# Sheet1.net
KiCad netlist of a schematic drawn in Altium Designer
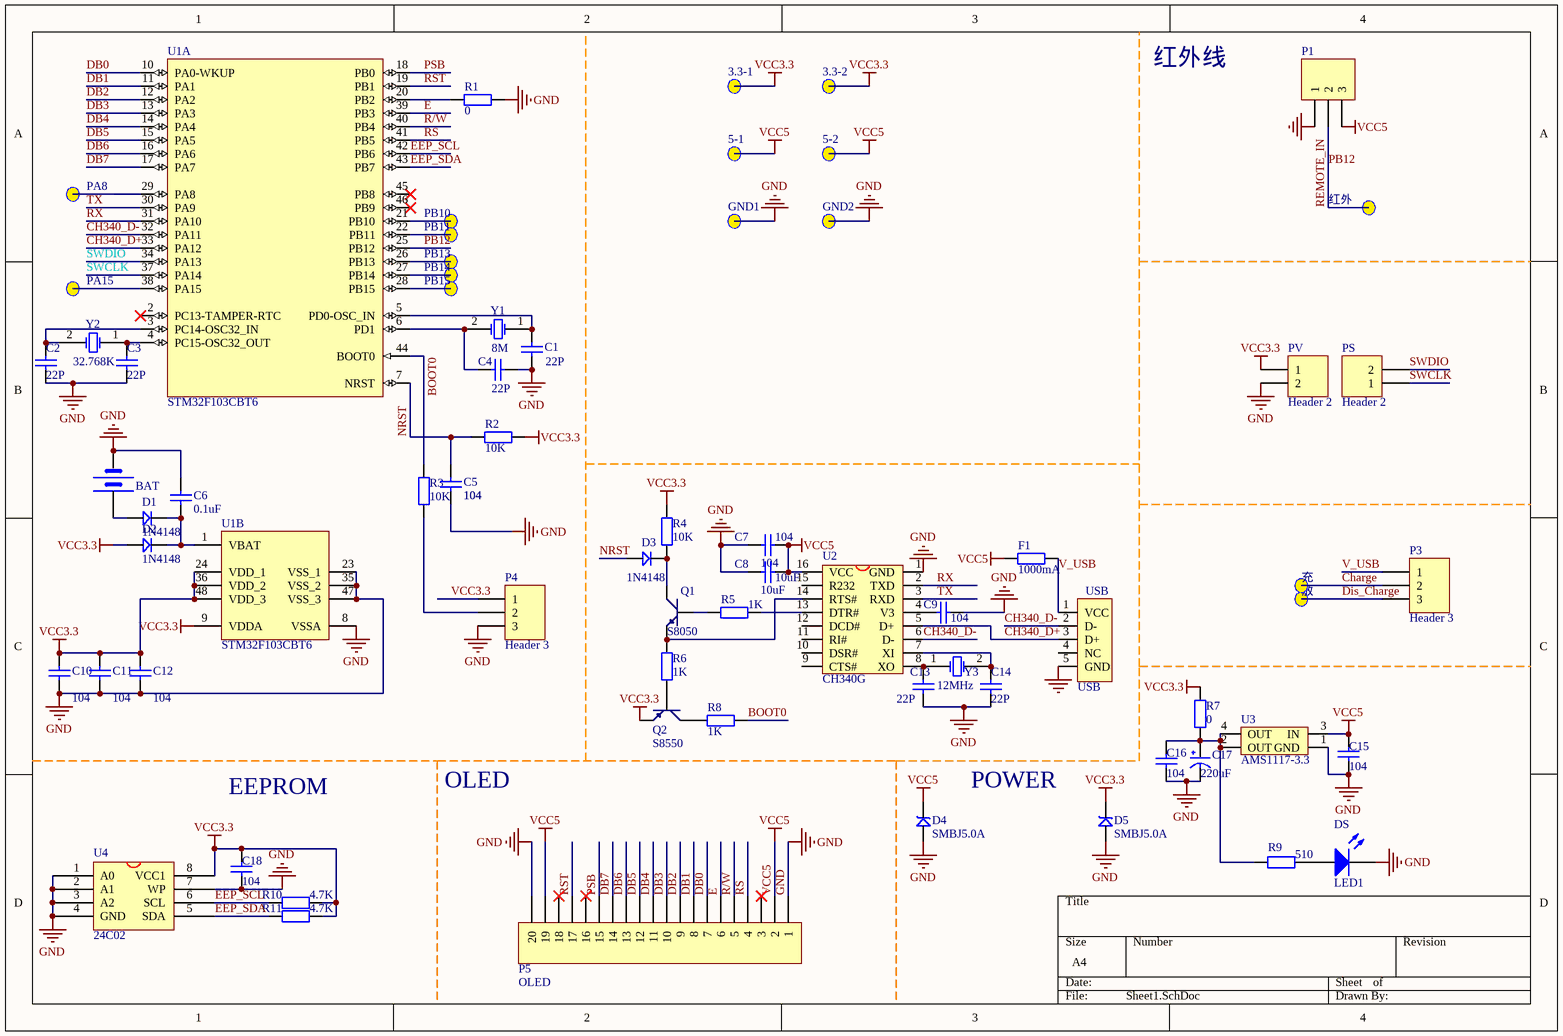
[diagram p0: Sheet1.SchDoc]

(export (version "E")
  (design (tool "Eeschema 10.0.6"))
  (components
    (comp (ref "3.3-1")
      (value "TEST_PAD")
      (footprint "pin1")
      (libsource (lib "EliteSTM32") (part "TEST_PAD"))
    )
    (comp (ref "3.3-2")
      (value "TEST_PAD")
      (footprint "pin1")
      (libsource (lib "EliteSTM32") (part "TEST_PAD"))
    )
    (comp (ref "5-1") (value "TEST_PAD") (footprint "pin1") (libsource (lib "EliteSTM32") (part "TEST_PAD")))
    (comp (ref "5-2") (value "TEST_PAD") (footprint "pin1") (libsource (lib "EliteSTM32") (part "TEST_PAD")))
    (comp (ref "BAT") (value "BATT") (footprint "BATM") (libsource (lib "EliteSTM32封装库") (part "BAT")))
    (comp (ref "C1")
      (value "22P")
      (footprint "0603p")
      (description "Capacitor")
      (fields (field (name "PUBLISHER") "Altium Limited"))
      (libsource (lib "Miscellaneous Devices") (part "Cap"))
    )
    (comp (ref "C2")
      (value "22P")
      (footprint "0603P")
      (description "Capacitor")
      (fields (field (name "PUBLISHER") "Altium Limited"))
      (libsource (lib "Miscellaneous Devices") (part "Cap"))
    )
    (comp (ref "C3")
      (value "22P")
      (footprint "0603P")
      (description "Capacitor")
      (fields (field (name "PUBLISHER") "Altium Limited"))
      (libsource (lib "Miscellaneous Devices") (part "Cap"))
    )
    (comp (ref "C4")
      (value "22P")
      (footprint "0603p")
      (description "Capacitor")
      (fields (field (name "PUBLISHER") "Altium Limited"))
      (libsource (lib "Miscellaneous Devices") (part "Cap"))
    )
    (comp (ref "C5")
      (value "104")
      (footprint "0603p")
      (description "Capacitor")
      (fields (field (name "ALTIUM_VALUE") "104") (field (name "PUBLISHER") "Altium Limited"))
      (libsource (lib "Miscellaneous Devices") (part "Cap"))
    )
    (comp (ref "C6")
      (value "0.1uF")
      (footprint "0603P")
      (description "Capacitor")
      (fields (field (name "PUBLISHER") "Altium Limited"))
      (libsource (lib "Miscellaneous Devices") (part "Cap"))
    )
    (comp (ref "C7")
      (value "104")
      (footprint "0603p")
      (description "Capacitor")
      (fields (field (name "ALTIUM_VALUE") "104") (field (name "PUBLISHER") "Altium Limited"))
      (libsource (lib "Miscellaneous Devices") (part "Cap"))
    )
    (comp (ref "C8")
      (value "10uF")
      (footprint "0603p")
      (description "Capacitor")
      (fields (field (name "ALTIUM_VALUE") "10uF") (field (name "PUBLISHER") "Altium Limited"))
      (libsource (lib "Miscellaneous Devices") (part "Cap"))
    )
    (comp (ref "C9")
      (value "104")
      (footprint "0603P")
      (description "Capacitor")
      (fields (field (name "PUBLISHER") "Altium Limited"))
      (libsource (lib "Miscellaneous Devices") (part "Cap"))
    )
    (comp (ref "C10")
      (value "104")
      (footprint "0603p")
      (description "Capacitor")
      (fields (field (name "PUBLISHER") "Altium Limited"))
      (libsource (lib "Miscellaneous Devices") (part "Cap"))
    )
    (comp (ref "C11")
      (value "104")
      (footprint "0603p")
      (description "Capacitor")
      (fields (field (name "PUBLISHER") "Altium Limited"))
      (libsource (lib "Miscellaneous Devices") (part "Cap"))
    )
    (comp (ref "C12")
      (value "104")
      (footprint "0603p")
      (description "Capacitor")
      (fields (field (name "PUBLISHER") "Altium Limited"))
      (libsource (lib "Miscellaneous Devices") (part "Cap"))
    )
    (comp (ref "C13")
      (value "22P")
      (footprint "0603P")
      (description "Capacitor")
      (fields (field (name "PUBLISHER") "Altium Limited"))
      (libsource (lib "Miscellaneous Devices") (part "Cap"))
    )
    (comp (ref "C14")
      (value "22P")
      (footprint "0603P")
      (description "Capacitor")
      (fields (field (name "PUBLISHER") "Altium Limited"))
      (libsource (lib "Miscellaneous Devices") (part "Cap"))
    )
    (comp (ref "C15")
      (value "104")
      (footprint "0603P")
      (description "Capacitor")
      (fields (field (name "PUBLISHER") "Altium Limited"))
      (libsource (lib "Miscellaneous Devices") (part "Cap"))
    )
    (comp (ref "C16")
      (value "104")
      (footprint "0603P")
      (description "Capacitor")
      (fields (field (name "PUBLISHER") "Altium Limited"))
      (libsource (lib "Miscellaneous Devices") (part "Cap"))
    )
    (comp (ref "C17") (value "220uF") (footprint "CC6.56.5") (libsource (lib "EliteSTM32封装库") (part "CAP")))
    (comp (ref "C18")
      (value "104")
      (footprint "0603P")
      (description "Capacitor")
      (fields (field (name "PUBLISHER") "Altium Limited"))
      (libsource (lib "Miscellaneous Devices") (part "Cap"))
    )
    (comp (ref "D1") (value "1N4148") (footprint "DIODE_SOP") (libsource (lib "EliteSTM32封装库") (part "D")))
    (comp (ref "D2") (value "1N4148") (footprint "DIODE_SOP") (libsource (lib "EliteSTM32封装库") (part "D")))
    (comp (ref "D3") (value "1N4148") (footprint "DIODE_SOP") (libsource (lib "EliteSTM32封装库") (part "D")))
    (comp (ref "D4")
      (value "SMBJ5.0A")
      (footprint "SMBJ")
      (description "TVS")
      (libsource (lib "EliteSTM32封装库") (part "SMBJ"))
    )
    (comp (ref "D5")
      (value "SMBJ5.0A")
      (footprint "SMBJ")
      (description "TVS")
      (libsource (lib "EliteSTM32封装库") (part "SMBJ"))
    )
    (comp (ref "DS")
      (value "LED1")
      (footprint "SMDLED")
      (description "Typical RED, GREEN, YELLOW, AMBER GaAs LED")
      (fields (field (name "PUBLISHER") "Altium Limited"))
      (libsource (lib "EliteSTM32封装库") (part "LED2"))
    )
    (comp (ref "F1")
      (value "1000mA")
      (footprint "1206")
      (description "Resistor")
      (fields (field (name "PUBLISHER") "Altium Limited"))
      (libsource (lib "") (part "Res2_1"))
    )
    (comp (ref "GND1") (value "TEST_PAD") (footprint "pin1") (libsource (lib "EliteSTM32") (part "TEST_PAD")))
    (comp (ref "GND2") (value "TEST_PAD") (footprint "pin1") (libsource (lib "EliteSTM32") (part "TEST_PAD")))
    (comp (ref "P1")
      (value "Header 3")
      (footprint "HDR1X3")
      (description "Header, 3-Pin")
      (fields (field (name "PUBLISHER") "Altium Limited"))
      (libsource (lib "") (part "Header 3_1"))
    )
    (comp (ref "P3")
      (value "Header 3")
      (footprint "HDR1X3")
      (description "Header, 3-Pin")
      (fields (field (name "PUBLISHER") "Altium Limited"))
      (libsource (lib "Miscellaneous Connectors") (part "Header 3"))
    )
    (comp (ref "P4")
      (value "Header 3")
      (footprint "2-1")
      (description "Header, 3-Pin")
      (fields (field (name "PUBLISHER") "Altium Limited"))
      (libsource (lib "Miscellaneous Connectors") (part "Header 3"))
    )
    (comp (ref "P5")
      (value "OLED")
      (footprint "HDR1X20")
      (description "Header, 20-Pin")
      (fields (field (name "PUBLISHER") "Altium Limited"))
      (libsource (lib "Miscellaneous Connectors") (part "Header 20"))
    )
    (comp (ref "PA8") (value "TEST_PAD") (footprint "pin1") (libsource (lib "EliteSTM32") (part "TEST_PAD")))
    (comp (ref "PA15") (value "TEST_PAD") (footprint "pin1") (libsource (lib "EliteSTM32") (part "TEST_PAD")))
    (comp (ref "PB10") (value "TEST_PAD") (footprint "pin1") (libsource (lib "EliteSTM32") (part "TEST_PAD")))
    (comp (ref "PB11") (value "TEST_PAD") (footprint "pin1") (libsource (lib "EliteSTM32") (part "TEST_PAD")))
    (comp (ref "PB13") (value "TEST_PAD") (footprint "pin1") (libsource (lib "EliteSTM32") (part "TEST_PAD")))
    (comp (ref "PB14") (value "TEST_PAD") (footprint "pin1") (libsource (lib "EliteSTM32") (part "TEST_PAD")))
    (comp (ref "PB15") (value "TEST_PAD") (footprint "pin1") (libsource (lib "EliteSTM32") (part "TEST_PAD")))
    (comp (ref "PS")
      (value "Header 2")
      (footprint "HDR1X2")
      (description "Header, 2-Pin")
      (fields (field (name "PUBLISHER") "Altium Limited"))
      (libsource (lib "Miscellaneous Connectors") (part "Header 2"))
    )
    (comp (ref "PV")
      (value "Header 2")
      (footprint "HDR1X2")
      (description "Header, 2-Pin")
      (fields (field (name "PUBLISHER") "Altium Limited"))
      (libsource (lib "") (part "Header 2_1"))
    )
    (comp (ref "Q1")
      (value "S8050")
      (footprint "SOT-23R")
      (description "8050/BCW846/BCW847")
      (libsource (lib "EliteSTM32") (part "NPN"))
    )
    (comp (ref "Q2")
      (value "S8550")
      (footprint "SOT-23R")
      (description "8550/BCW68")
      (libsource (lib "EliteSTM32") (part "PNP"))
    )
    (comp (ref "R1")
      (value "0")
      (footprint "0603p")
      (description "Resistor")
      (fields (field (name "PUBLISHER") "Altium Limited"))
      (libsource (lib "Miscellaneous Devices") (part "Res2"))
    )
    (comp (ref "R2")
      (value "10K")
      (footprint "0603p")
      (description "Resistor")
      (fields (field (name "PUBLISHER") "Altium Limited"))
      (libsource (lib "Miscellaneous Devices") (part "Res2"))
    )
    (comp (ref "R3")
      (value "10K")
      (footprint "0603p")
      (description "Resistor")
      (fields (field (name "PUBLISHER") "Altium Limited"))
      (libsource (lib "") (part "Res2_2"))
    )
    (comp (ref "R4")
      (value "10K")
      (footprint "0603p")
      (description "Resistor")
      (fields (field (name "PUBLISHER") "Altium Limited"))
      (libsource (lib "") (part "Res2_2"))
    )
    (comp (ref "R5")
      (value "1K")
      (footprint "0603p")
      (description "Resistor")
      (fields (field (name "PUBLISHER") "Altium Limited"))
      (libsource (lib "Miscellaneous Devices") (part "Res2"))
    )
    (comp (ref "R6")
      (value "1K")
      (footprint "0603p")
      (description "Resistor")
      (fields (field (name "PUBLISHER") "Altium Limited"))
      (libsource (lib "") (part "Res2_2"))
    )
    (comp (ref "R7")
      (value "0")
      (footprint "0603P")
      (description "Resistor")
      (fields (field (name "PUBLISHER") "Altium Limited"))
      (libsource (lib "") (part "Res2_2"))
    )
    (comp (ref "R8")
      (value "1K")
      (footprint "0603p")
      (description "Resistor")
      (fields (field (name "PUBLISHER") "Altium Limited"))
      (libsource (lib "") (part "Res2_1"))
    )
    (comp (ref "R9")
      (value "510")
      (footprint "0603p")
      (description "Resistor")
      (fields (field (name "PUBLISHER") "Altium Limited"))
      (libsource (lib "Miscellaneous Devices") (part "Res2"))
    )
    (comp (ref "R10")
      (value "4.7K")
      (footprint "0603P")
      (description "Resistor")
      (fields (field (name "PUBLISHER") "Altium Limited"))
      (libsource (lib "Miscellaneous Devices") (part "Res2"))
    )
    (comp (ref "R11")
      (value "4.7K")
      (footprint "0603P")
      (description "Resistor")
      (fields (field (name "PUBLISHER") "Altium Limited"))
      (libsource (lib "Miscellaneous Devices") (part "Res2"))
    )
    (comp (ref "U1")
      (value "STM32F103CBT6")
      (footprint "LQFP48_M")
      (libsource (lib "STMicroelectronics STM32 F1") (part "STM32F103CBT6"))
    )
    (comp (ref "U2")
      (value "CH340G")
      (footprint "SOP16M")
      (description "USB2UART")
      (libsource (lib "EliteSTM32") (part "CH340G"))
    )
    (comp (ref "U3")
      (value "AMS1117-3.3")
      (footprint "AMS1117")
      (libsource (lib "EliteSTM32封装库") (part "AMS1117"))
    )
    (comp (ref "U4") (value "24C02") (footprint "SOP-8") (libsource (lib "cabinet") (part "24C256")))
    (comp (ref "USB")
      (value "USB")
      (footprint "USB/SM0.8-6H5")
      (libsource (lib "EliteSTM32封装库") (part "USB5"))
    )
    (comp (ref "Y1")
      (value "8M")
      (footprint "XTAL_US")
      (description "Crystal Oscillator")
      (fields (field (name "PUBLISHER") "Altium Limited"))
      (libsource (lib "Miscellaneous Devices") (part "XTAL"))
    )
    (comp (ref "Y2")
      (value "32.768K")
      (footprint "XTAL32")
      (description "Crystal Oscillator")
      (fields (field (name "PUBLISHER") "Altium Limited"))
      (libsource (lib "Miscellaneous Devices") (part "XTAL"))
    )
    (comp (ref "Y3")
      (value "12MHz")
      (footprint "XTAL_US")
      (description "Crystal Oscillator")
      (fields (field (name "PUBLISHER") "Altium Limited"))
      (libsource (lib "EliteSTM32") (part "XTAL"))
    )
    (comp (ref "充") (value "TEST_PAD") (footprint "pin1") (libsource (lib "EliteSTM32") (part "TEST_PAD")))
    (comp (ref "放") (value "TEST_PAD") (footprint "pin1") (libsource (lib "EliteSTM32") (part "TEST_PAD")))
    (comp (ref "红外") (value "TEST_PAD") (footprint "pin1") (libsource (lib "EliteSTM32") (part "TEST_PAD")))
  )
  (nets
    (net (code "1") (name "/BOOT0") (class "Default")
      (node (ref "R3") (pin "2") (pinfunction "2_2") (pintype "passive"))
      (node (ref "R8") (pin "1") (pinfunction "1_1") (pintype "passive"))
      (node (ref "U1") (pin "44") (pinfunction "BOOT0_44") (pintype "input"))
    )
    (net (code "2") (name "/CH340_D+") (class "Default")
      (node (ref "U1") (pin "33") (pinfunction "PA12_33") (pintype "bidirectional"))
      (node (ref "U2") (pin "5") (pinfunction "D+_5") (pintype "passive"))
      (node (ref "USB") (pin "3") (pinfunction "D+_3") (pintype "passive"))
    )
    (net (code "3") (name "/CH340_D-") (class "Default")
      (node (ref "U1") (pin "32") (pinfunction "PA11_32") (pintype "bidirectional"))
      (node (ref "U2") (pin "6") (pinfunction "D-_6") (pintype "passive"))
      (node (ref "USB") (pin "2") (pinfunction "D-_2") (pintype "passive"))
    )
    (net (code "4") (name "/Charge") (class "Default")
      (node (ref "P3") (pin "2") (pinfunction "2_2") (pintype "passive"))
      (node (ref "充") (pin "1") (pinfunction "1_1") (pintype "passive"))
    )
    (net (code "5") (name "/DB0") (class "Default")
      (node (ref "P5") (pin "7") (pinfunction "7_7") (pintype "passive"))
      (node (ref "U1") (pin "10") (pinfunction "PA0-WKUP_10") (pintype "bidirectional"))
    )
    (net (code "6") (name "/DB1") (class "Default")
      (node (ref "P5") (pin "8") (pinfunction "8_8") (pintype "passive"))
      (node (ref "U1") (pin "11") (pinfunction "PA1_11") (pintype "bidirectional"))
    )
    (net (code "7") (name "/DB2") (class "Default")
      (node (ref "P5") (pin "9") (pinfunction "9_9") (pintype "passive"))
      (node (ref "U1") (pin "12") (pinfunction "PA2_12") (pintype "bidirectional"))
    )
    (net (code "8") (name "/DB3") (class "Default")
      (node (ref "P5") (pin "10") (pinfunction "10_10") (pintype "passive"))
      (node (ref "U1") (pin "13") (pinfunction "PA3_13") (pintype "bidirectional"))
    )
    (net (code "9") (name "/DB4") (class "Default")
      (node (ref "P5") (pin "11") (pinfunction "11_11") (pintype "passive"))
      (node (ref "U1") (pin "14") (pinfunction "PA4_14") (pintype "bidirectional"))
    )
    (net (code "10") (name "/DB5") (class "Default")
      (node (ref "P5") (pin "12") (pinfunction "12_12") (pintype "passive"))
      (node (ref "U1") (pin "15") (pinfunction "PA5_15") (pintype "bidirectional"))
    )
    (net (code "11") (name "/DB6") (class "Default")
      (node (ref "P5") (pin "13") (pinfunction "13_13") (pintype "passive"))
      (node (ref "U1") (pin "16") (pinfunction "PA6_16") (pintype "bidirectional"))
    )
    (net (code "12") (name "/DB7") (class "Default")
      (node (ref "P5") (pin "14") (pinfunction "14_14") (pintype "passive"))
      (node (ref "U1") (pin "17") (pinfunction "PA7_17") (pintype "bidirectional"))
    )
    (net (code "13") (name "/Dis_Charge") (class "Default")
      (node (ref "P3") (pin "3") (pinfunction "3_3") (pintype "passive"))
      (node (ref "放") (pin "1") (pinfunction "1_1") (pintype "passive"))
    )
    (net (code "14") (name "/E") (class "Default")
      (node (ref "P5") (pin "6") (pinfunction "6_6") (pintype "passive"))
      (node (ref "U1") (pin "39") (pinfunction "PB3_39") (pintype "bidirectional"))
    )
    (net (code "15") (name "/EEP_SCL") (class "Default")
      (node (ref "R10") (pin "1") (pinfunction "1_1") (pintype "passive"))
      (node (ref "U1") (pin "42") (pinfunction "PB6_42") (pintype "bidirectional"))
      (node (ref "U4") (pin "6") (pinfunction "SCL_6") (pintype "passive"))
    )
    (net (code "16") (name "/EEP_SDA") (class "Default")
      (node (ref "R11") (pin "1") (pinfunction "1_1") (pintype "passive"))
      (node (ref "U1") (pin "43") (pinfunction "PB7_43") (pintype "bidirectional"))
      (node (ref "U4") (pin "5") (pinfunction "SDA_5") (pintype "passive"))
    )
    (net (code "17") (name "/NRST") (class "Default")
      (node (ref "C5") (pin "2") (pinfunction "2_2") (pintype "passive"))
      (node (ref "D3") (pin "1") (pintype "passive"))
      (node (ref "R2") (pin "1") (pinfunction "1_1") (pintype "passive"))
      (node (ref "U1") (pin "7") (pinfunction "NRST_7") (pintype "bidirectional"))
    )
    (net (code "18") (name "/PB12") (class "Default")
      (node (ref "P1") (pin "2") (pinfunction "2_2") (pintype "passive"))
      (node (ref "U1") (pin "25") (pinfunction "PB12_25") (pintype "bidirectional"))
      (node (ref "红外") (pin "1") (pinfunction "1_1") (pintype "passive"))
    )
    (net (code "19") (name "/PSB") (class "Default")
      (node (ref "P5") (pin "15") (pinfunction "15_15") (pintype "passive"))
      (node (ref "U1") (pin "18") (pinfunction "PB0_18") (pintype "bidirectional"))
    )
    (net (code "20") (name "/RS") (class "Default")
      (node (ref "P5") (pin "4") (pinfunction "4_4") (pintype "passive"))
      (node (ref "U1") (pin "41") (pinfunction "PB5_41") (pintype "bidirectional"))
    )
    (net (code "21") (name "/RST") (class "Default")
      (node (ref "P5") (pin "17") (pinfunction "17_17") (pintype "passive"))
      (node (ref "U1") (pin "19") (pinfunction "PB1_19") (pintype "bidirectional"))
    )
    (net (code "22") (name "/RX") (class "Default")
      (node (ref "U1") (pin "31") (pinfunction "PA10_31") (pintype "bidirectional"))
      (node (ref "U2") (pin "2") (pinfunction "TXD_2") (pintype "passive"))
    )
    (net (code "23") (name "/R{slash}W") (class "Default")
      (node (ref "P5") (pin "5") (pinfunction "5_5") (pintype "passive"))
      (node (ref "U1") (pin "40") (pinfunction "PB4_40") (pintype "bidirectional"))
    )
    (net (code "24") (name "/SWCLK") (class "Default")
      (node (ref "PS") (pin "1") (pinfunction "1_1") (pintype "passive"))
      (node (ref "U1") (pin "37") (pinfunction "PA14_37") (pintype "bidirectional"))
    )
    (net (code "25") (name "/SWDIO") (class "Default")
      (node (ref "PS") (pin "2") (pinfunction "2_2") (pintype "passive"))
      (node (ref "U1") (pin "34") (pinfunction "PA13_34") (pintype "bidirectional"))
    )
    (net (code "26") (name "/TX") (class "Default")
      (node (ref "U1") (pin "30") (pinfunction "PA9_30") (pintype "bidirectional"))
      (node (ref "U2") (pin "3") (pinfunction "RXD_3") (pintype "passive"))
    )
    (net (code "27") (name "/V_USB") (class "Default")
      (node (ref "F1") (pin "1") (pinfunction "1_1") (pintype "passive"))
      (node (ref "P3") (pin "1") (pinfunction "1_1") (pintype "passive"))
      (node (ref "USB") (pin "1") (pinfunction "VCC_1") (pintype "passive"))
    )
    (net (code "28") (name "GND") (class "Default")
      (node (ref "BAT") (pin "2") (pinfunction "GND_2") (pintype "passive"))
      (node (ref "C1") (pin "2") (pinfunction "2_2") (pintype "passive"))
      (node (ref "C10") (pin "1") (pinfunction "1_1") (pintype "passive"))
      (node (ref "C11") (pin "1") (pinfunction "1_1") (pintype "passive"))
      (node (ref "C12") (pin "1") (pinfunction "1_1") (pintype "passive"))
      (node (ref "C13") (pin "2") (pinfunction "2_2") (pintype "passive"))
      (node (ref "C14") (pin "2") (pinfunction "2_2") (pintype "passive"))
      (node (ref "C15") (pin "1") (pinfunction "1_1") (pintype "passive"))
      (node (ref "C16") (pin "1") (pinfunction "1_1") (pintype "passive"))
      (node (ref "C17") (pin "2") (pinfunction "GND_2") (pintype "passive"))
      (node (ref "C18") (pin "1") (pinfunction "1_1") (pintype "passive"))
      (node (ref "C2") (pin "2") (pinfunction "2_2") (pintype "passive"))
      (node (ref "C3") (pin "2") (pinfunction "2_2") (pintype "passive"))
      (node (ref "C4") (pin "1") (pinfunction "1_1") (pintype "passive"))
      (node (ref "C5") (pin "1") (pinfunction "1_1") (pintype "passive"))
      (node (ref "C6") (pin "1") (pinfunction "1_1") (pintype "passive"))
      (node (ref "C7") (pin "2") (pinfunction "2_2") (pintype "passive"))
      (node (ref "C8") (pin "2") (pinfunction "2_2") (pintype "passive"))
      (node (ref "C9") (pin "1") (pinfunction "1_1") (pintype "passive"))
      (node (ref "D4") (pin "1") (pintype "passive"))
      (node (ref "D5") (pin "1") (pintype "passive"))
      (node (ref "DS") (pin "2") (pinfunction "K_2") (pintype "passive"))
      (node (ref "GND1") (pin "1") (pinfunction "1_1") (pintype "passive"))
      (node (ref "GND2") (pin "1") (pinfunction "1_1") (pintype "passive"))
      (node (ref "P1") (pin "1") (pinfunction "1_1") (pintype "passive"))
      (node (ref "P4") (pin "3") (pinfunction "3_3") (pintype "passive"))
      (node (ref "P5") (pin "1") (pinfunction "1_1") (pintype "passive"))
      (node (ref "P5") (pin "20") (pinfunction "20_20") (pintype "passive"))
      (node (ref "PV") (pin "2") (pinfunction "2_2") (pintype "passive"))
      (node (ref "R1") (pin "2") (pinfunction "2_2") (pintype "passive"))
      (node (ref "U1") (pin "23") (pinfunction "VSS_1_23") (pintype "power_in"))
      (node (ref "U1") (pin "35") (pinfunction "VSS_2_35") (pintype "power_in"))
      (node (ref "U1") (pin "47") (pinfunction "VSS_3_47") (pintype "power_in"))
      (node (ref "U1") (pin "8") (pinfunction "VSSA_8") (pintype "power_in"))
      (node (ref "U2") (pin "1") (pinfunction "GND_1") (pintype "passive"))
      (node (ref "U3") (pin "1") (pinfunction "GND_1") (pintype "passive"))
      (node (ref "U4") (pin "1") (pinfunction "A0_1") (pintype "passive"))
      (node (ref "U4") (pin "2") (pinfunction "A1_2") (pintype "passive"))
      (node (ref "U4") (pin "3") (pinfunction "A2_3") (pintype "passive"))
      (node (ref "U4") (pin "4") (pinfunction "GND_4") (pintype "passive"))
      (node (ref "U4") (pin "7") (pinfunction "WP_7") (pintype "passive"))
      (node (ref "USB") (pin "5") (pinfunction "GND_5") (pintype "passive"))
    )
    (net (code "29") (name "Net-(BAT-VCC)") (class "Default")
      (node (ref "BAT") (pin "1") (pinfunction "VCC_1") (pintype "passive"))
      (node (ref "D1") (pin "1") (pintype "passive"))
    )
    (net (code "30") (name "Net-(C17-VCC)") (class "Default")
      (node (ref "C16") (pin "2") (pinfunction "2_2") (pintype "passive"))
      (node (ref "C17") (pin "1") (pinfunction "VCC_1") (pintype "passive"))
      (node (ref "R7") (pin "1") (pinfunction "1_1") (pintype "passive"))
      (node (ref "R9") (pin "1") (pinfunction "1_1") (pintype "passive"))
      (node (ref "U3") (pin "2") (pinfunction "OUT_2") (pintype "passive"))
      (node (ref "U3") (pin "4") (pinfunction "OUT_4") (pintype "passive"))
    )
    (net (code "31") (name "Net-(DS-A)") (class "Default")
      (node (ref "DS") (pin "1") (pinfunction "A_1") (pintype "passive"))
      (node (ref "R9") (pin "2") (pinfunction "2_2") (pintype "passive"))
    )
    (net (code "32") (name "Net-(P4-Pad2)") (class "Default")
      (node (ref "P4") (pin "2") (pinfunction "2_2") (pintype "passive"))
      (node (ref "R3") (pin "1") (pinfunction "1_1") (pintype "passive"))
    )
    (net (code "33") (name "Net-(Q1-B)") (class "Default")
      (node (ref "Q1") (pin "2") (pinfunction "B_2") (pintype "passive"))
      (node (ref "R5") (pin "1") (pinfunction "1_1") (pintype "passive"))
    )
    (net (code "34") (name "Net-(Q1-C)") (class "Default")
      (node (ref "D3") (pin "2") (pintype "passive"))
      (node (ref "Q1") (pin "3") (pinfunction "C_3") (pintype "passive"))
      (node (ref "R4") (pin "1") (pinfunction "1_1") (pintype "passive"))
    )
    (net (code "35") (name "Net-(Q1-E)") (class "Default")
      (node (ref "Q1") (pin "1") (pinfunction "E_1") (pintype "passive"))
      (node (ref "R6") (pin "2") (pinfunction "2_2") (pintype "passive"))
      (node (ref "U2") (pin "14") (pinfunction "RTS#_14") (pintype "passive"))
    )
    (net (code "36") (name "Net-(Q2-B)") (class "Default")
      (node (ref "Q2") (pin "2") (pinfunction "B_2") (pintype "passive"))
      (node (ref "R6") (pin "1") (pinfunction "1_1") (pintype "passive"))
    )
    (net (code "37") (name "Net-(Q2-C)") (class "Default")
      (node (ref "Q2") (pin "3") (pinfunction "C_3") (pintype "passive"))
      (node (ref "R8") (pin "2") (pinfunction "2_2") (pintype "passive"))
    )
    (net (code "38") (name "Net-(U1A-PA8)") (class "Default")
      (node (ref "PA8") (pin "1") (pinfunction "1_1") (pintype "passive"))
      (node (ref "U1") (pin "29") (pinfunction "PA8_29") (pintype "bidirectional"))
    )
    (net (code "39") (name "Net-(U1A-PA15)") (class "Default")
      (node (ref "PA15") (pin "1") (pinfunction "1_1") (pintype "passive"))
      (node (ref "U1") (pin "38") (pinfunction "PA15_38") (pintype "bidirectional"))
    )
    (net (code "40") (name "Net-(U1A-PB2)") (class "Default")
      (node (ref "R1") (pin "1") (pinfunction "1_1") (pintype "passive"))
      (node (ref "U1") (pin "20") (pinfunction "PB2_20") (pintype "bidirectional"))
    )
    (net (code "41") (name "Net-(U1A-PB10)") (class "Default")
      (node (ref "PB10") (pin "1") (pinfunction "1_1") (pintype "passive"))
      (node (ref "U1") (pin "21") (pinfunction "PB10_21") (pintype "bidirectional"))
    )
    (net (code "42") (name "Net-(U1A-PB11)") (class "Default")
      (node (ref "PB11") (pin "1") (pinfunction "1_1") (pintype "passive"))
      (node (ref "U1") (pin "22") (pinfunction "PB11_22") (pintype "bidirectional"))
    )
    (net (code "43") (name "Net-(U1A-PB13)") (class "Default")
      (node (ref "PB13") (pin "1") (pinfunction "1_1") (pintype "passive"))
      (node (ref "U1") (pin "26") (pinfunction "PB13_26") (pintype "bidirectional"))
    )
    (net (code "44") (name "Net-(U1A-PB14)") (class "Default")
      (node (ref "PB14") (pin "1") (pinfunction "1_1") (pintype "passive"))
      (node (ref "U1") (pin "27") (pinfunction "PB14_27") (pintype "bidirectional"))
    )
    (net (code "45") (name "Net-(U1A-PB15)") (class "Default")
      (node (ref "PB15") (pin "1") (pinfunction "1_1") (pintype "passive"))
      (node (ref "U1") (pin "28") (pinfunction "PB15_28") (pintype "bidirectional"))
    )
    (net (code "46") (name "Net-(U1A-PC14-OSC32_IN)") (class "Default")
      (node (ref "C2") (pin "1") (pinfunction "1_1") (pintype "passive"))
      (node (ref "U1") (pin "3") (pinfunction "PC14-OSC32_IN_3") (pintype "bidirectional"))
      (node (ref "Y2") (pin "2") (pinfunction "OSC2_2") (pintype "passive"))
    )
    (net (code "47") (name "Net-(U1A-PC15-OSC32_OUT)") (class "Default")
      (node (ref "C3") (pin "1") (pinfunction "1_1") (pintype "passive"))
      (node (ref "U1") (pin "4") (pinfunction "PC15-OSC32_OUT_4") (pintype "bidirectional"))
      (node (ref "Y2") (pin "1") (pinfunction "OSC1_1") (pintype "passive"))
    )
    (net (code "48") (name "Net-(U1A-PD0-OSC_IN)") (class "Default")
      (node (ref "C1") (pin "1") (pinfunction "1_1") (pintype "passive"))
      (node (ref "U1") (pin "5") (pinfunction "PD0-OSC_IN_5") (pintype "bidirectional"))
      (node (ref "Y1") (pin "1") (pinfunction "OSC1_1") (pintype "passive"))
    )
    (net (code "49") (name "Net-(U1A-PD1)") (class "Default")
      (node (ref "C4") (pin "2") (pinfunction "2_2") (pintype "passive"))
      (node (ref "U1") (pin "6") (pinfunction "PD1_6") (pintype "bidirectional"))
      (node (ref "Y1") (pin "2") (pinfunction "OSC2_2") (pintype "passive"))
    )
    (net (code "50") (name "Net-(U1B-VBAT)") (class "Default")
      (node (ref "C6") (pin "2") (pinfunction "2_2") (pintype "passive"))
      (node (ref "D1") (pin "2") (pintype "passive"))
      (node (ref "D2") (pin "2") (pintype "passive"))
      (node (ref "U1") (pin "1") (pinfunction "VBAT_1") (pintype "power_in"))
    )
    (net (code "51") (name "Net-(U2-DTR#)") (class "Default")
      (node (ref "R5") (pin "2") (pinfunction "2_2") (pintype "passive"))
      (node (ref "U2") (pin "13") (pinfunction "DTR#_13") (pintype "passive"))
    )
    (net (code "52") (name "Net-(U2-V3)") (class "Default")
      (node (ref "C9") (pin "2") (pinfunction "2_2") (pintype "passive"))
      (node (ref "U2") (pin "4") (pinfunction "V3_4") (pintype "passive"))
    )
    (net (code "53") (name "Net-(U2-XI)") (class "Default")
      (node (ref "C14") (pin "1") (pinfunction "1_1") (pintype "passive"))
      (node (ref "U2") (pin "7") (pinfunction "XI_7") (pintype "passive"))
      (node (ref "Y3") (pin "2") (pinfunction "OSC2_2") (pintype "passive"))
    )
    (net (code "54") (name "Net-(U2-XO)") (class "Default")
      (node (ref "C13") (pin "1") (pinfunction "1_1") (pintype "passive"))
      (node (ref "U2") (pin "8") (pinfunction "XO_8") (pintype "passive"))
      (node (ref "Y3") (pin "1") (pinfunction "OSC1_1") (pintype "passive"))
    )
    (net (code "55") (name "VCC3.3") (class "Default")
      (node (ref "3.3-1") (pin "1") (pinfunction "1_1") (pintype "passive"))
      (node (ref "3.3-2") (pin "1") (pinfunction "1_1") (pintype "passive"))
      (node (ref "C10") (pin "2") (pinfunction "2_2") (pintype "passive"))
      (node (ref "C11") (pin "2") (pinfunction "2_2") (pintype "passive"))
      (node (ref "C12") (pin "2") (pinfunction "2_2") (pintype "passive"))
      (node (ref "C18") (pin "2") (pinfunction "2_2") (pintype "passive"))
      (node (ref "D2") (pin "1") (pintype "passive"))
      (node (ref "D5") (pin "2") (pintype "passive"))
      (node (ref "P4") (pin "1") (pinfunction "1_1") (pintype "passive"))
      (node (ref "PV") (pin "1") (pinfunction "1_1") (pintype "passive"))
      (node (ref "Q2") (pin "1") (pinfunction "E_1") (pintype "passive"))
      (node (ref "R10") (pin "2") (pinfunction "2_2") (pintype "passive"))
      (node (ref "R11") (pin "2") (pinfunction "2_2") (pintype "passive"))
      (node (ref "R2") (pin "2") (pinfunction "2_2") (pintype "passive"))
      (node (ref "R4") (pin "2") (pinfunction "2_2") (pintype "passive"))
      (node (ref "R7") (pin "2") (pinfunction "2_2") (pintype "passive"))
      (node (ref "U1") (pin "24") (pinfunction "VDD_1_24") (pintype "power_in"))
      (node (ref "U1") (pin "36") (pinfunction "VDD_2_36") (pintype "power_in"))
      (node (ref "U1") (pin "48") (pinfunction "VDD_3_48") (pintype "power_in"))
      (node (ref "U1") (pin "9") (pinfunction "VDDA_9") (pintype "power_in"))
      (node (ref "U4") (pin "8") (pinfunction "VCC1_8") (pintype "passive"))
    )
    (net (code "56") (name "VCC5") (class "Default")
      (node (ref "5-1") (pin "1") (pinfunction "1_1") (pintype "passive"))
      (node (ref "5-2") (pin "1") (pinfunction "1_1") (pintype "passive"))
      (node (ref "C15") (pin "2") (pinfunction "2_2") (pintype "passive"))
      (node (ref "C7") (pin "1") (pinfunction "1_1") (pintype "passive"))
      (node (ref "C8") (pin "1") (pinfunction "1_1") (pintype "passive"))
      (node (ref "D4") (pin "2") (pintype "passive"))
      (node (ref "F1") (pin "2") (pinfunction "2_2") (pintype "passive"))
      (node (ref "P1") (pin "3") (pinfunction "3_3") (pintype "passive"))
      (node (ref "P5") (pin "19") (pinfunction "19_19") (pintype "passive"))
      (node (ref "P5") (pin "2") (pinfunction "2_2") (pintype "passive"))
      (node (ref "U2") (pin "16") (pinfunction "VCC_16") (pintype "passive"))
      (node (ref "U3") (pin "3") (pinfunction "IN_3") (pintype "passive"))
    )
    (net (code "57") (name "unconnected-(P5-Pad3)") (class "Default")
      (node (ref "P5") (pin "3") (pinfunction "3_3") (pintype "passive+no_connect"))
    )
    (net (code "58") (name "unconnected-(P5-Pad16)") (class "Default")
      (node (ref "P5") (pin "16") (pinfunction "16_16") (pintype "passive+no_connect"))
    )
    (net (code "59") (name "unconnected-(P5-Pad18)") (class "Default")
      (node (ref "P5") (pin "18") (pinfunction "18_18") (pintype "passive+no_connect"))
    )
    (net (code "60") (name "unconnected-(U1A-PB8-Pad45)") (class "Default")
      (node (ref "U1") (pin "45") (pinfunction "PB8_45") (pintype "bidirectional+no_connect"))
    )
    (net (code "61") (name "unconnected-(U1A-PB9-Pad46)") (class "Default")
      (node (ref "U1") (pin "46") (pinfunction "PB9_46") (pintype "bidirectional+no_connect"))
    )
    (net (code "62") (name "unconnected-(U1A-PC13-TAMPER-RTC-Pad2)") (class "Default")
      (node (ref "U1") (pin "2") (pinfunction "PC13-TAMPER-RTC_2") (pintype "bidirectional+no_connect"))
    )
    (net (code "63") (name "unconnected-(U2-CTS#-Pad9)") (class "Default")
      (node (ref "U2") (pin "9") (pinfunction "CTS#_9") (pintype "passive"))
    )
    (net (code "64") (name "unconnected-(U2-DCD#-Pad12)") (class "Default")
      (node (ref "U2") (pin "12") (pinfunction "DCD#_12") (pintype "passive"))
    )
    (net (code "65") (name "unconnected-(U2-DSR#-Pad10)") (class "Default")
      (node (ref "U2") (pin "10") (pinfunction "DSR#_10") (pintype "passive"))
    )
    (net (code "66") (name "unconnected-(U2-R232-Pad15)") (class "Default")
      (node (ref "U2") (pin "15") (pinfunction "R232_15") (pintype "passive"))
    )
    (net (code "67") (name "unconnected-(U2-RI#-Pad11)") (class "Default")
      (node (ref "U2") (pin "11") (pinfunction "RI#_11") (pintype "passive"))
    )
    (net (code "68") (name "unconnected-(USB-NC-Pad4)") (class "Default")
      (node (ref "USB") (pin "4") (pinfunction "NC_4") (pintype "passive"))
    )
  )
)
